# SMD_cree_driver_led-mosfet0024-GoldPhoen.net
KiCad netlist of a schematic drawn in EAGLE
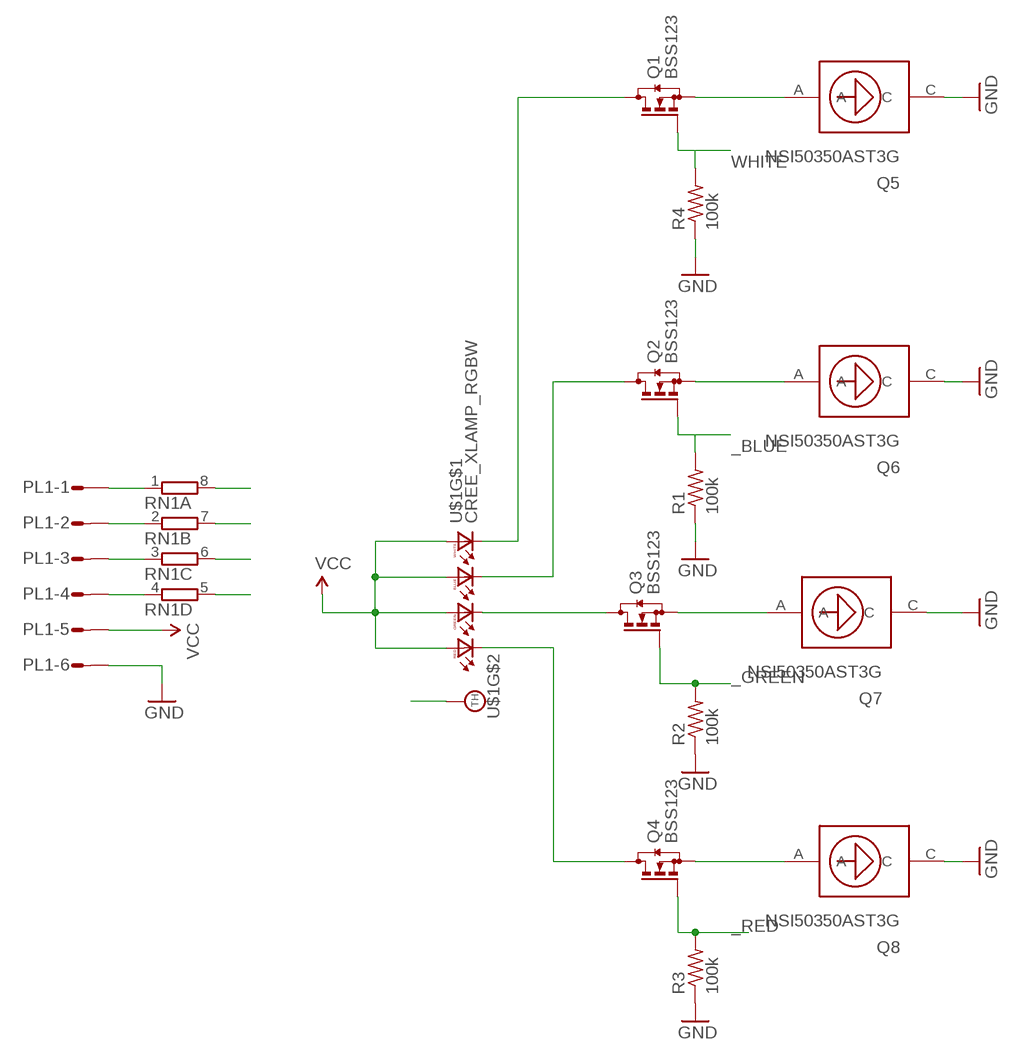
[diagram p0: schematic, sheet 1]

(export (version "E")
  (design (tool "Eeschema 10.0.6"))
  (components
    (comp (ref "PL1")
      (value "DF3-06R")
      (footprint "eagle-import:DF3R-06")
      (libsource (lib "eagle-import") (part "DF3-06R"))
    )
    (comp (ref "Q1")
      (value "BSS123")
      (footprint "eagle-import:SOT23")
      (libsource (lib "eagle-import") (part "BSS123"))
    )
    (comp (ref "Q2")
      (value "BSS123")
      (footprint "eagle-import:SOT23")
      (libsource (lib "eagle-import") (part "BSS123"))
    )
    (comp (ref "Q3")
      (value "BSS123")
      (footprint "eagle-import:SOT23")
      (libsource (lib "eagle-import") (part "BSS123"))
    )
    (comp (ref "Q4")
      (value "BSS123")
      (footprint "eagle-import:SOT23")
      (libsource (lib "eagle-import") (part "BSS123"))
    )
    (comp (ref "Q5")
      (value "NSI50350AST3G")
      (footprint "eagle-import:SMC-2")
      (libsource (lib "eagle-import") (part "NSI50350AST3G"))
    )
    (comp (ref "Q6")
      (value "NSI50350AST3G")
      (footprint "eagle-import:SMC-2")
      (libsource (lib "eagle-import") (part "NSI50350AST3G"))
    )
    (comp (ref "Q7")
      (value "NSI50350AST3G")
      (footprint "eagle-import:SMC-2")
      (libsource (lib "eagle-import") (part "NSI50350AST3G"))
    )
    (comp (ref "Q8")
      (value "NSI50350AST3G")
      (footprint "eagle-import:SMC-2")
      (libsource (lib "eagle-import") (part "NSI50350AST3G"))
    )
    (comp (ref "R1")
      (value "100k")
      (footprint "eagle-import:R0402")
      (libsource (lib "eagle-import") (part "R-US_R0402"))
    )
    (comp (ref "R2")
      (value "100k")
      (footprint "eagle-import:R0402")
      (libsource (lib "eagle-import") (part "R-US_R0402"))
    )
    (comp (ref "R3")
      (value "100k")
      (footprint "eagle-import:R0402")
      (libsource (lib "eagle-import") (part "R-US_R0402"))
    )
    (comp (ref "R4")
      (value "100k")
      (footprint "eagle-import:R0402")
      (libsource (lib "eagle-import") (part "R-US_R0402"))
    )
    (comp (ref "RN1")
      (value "4R-N0603-ARC")
      (footprint "eagle-import:0603-ARC")
      (libsource (lib "eagle-import") (part "4R-N0603-ARC"))
    )
    (comp (ref "U$1")
      (value "CREE_XLAMP_RGBW")
      (footprint "eagle-import:CREE_XLAMP_XML")
      (libsource (lib "eagle-import") (part "CREE_XLAMP_RGBW"))
    )
  )
  (nets
    (net (code "1") (name "/WHITE") (class "Default")
      (node (ref "Q1") (pin "1") (pinfunction "G_1") (pintype "passive"))
      (node (ref "R4") (pin "2") (pinfunction "2_2") (pintype "passive"))
      (node (ref "RN1") (pin "8") (pinfunction "2_8") (pintype "passive"))
    )
    (net (code "2") (name "/_BLUE") (class "Default")
      (node (ref "Q2") (pin "1") (pinfunction "G_1") (pintype "passive"))
      (node (ref "R1") (pin "2") (pinfunction "2_2") (pintype "passive"))
      (node (ref "RN1") (pin "6") (pinfunction "2_6") (pintype "passive"))
    )
    (net (code "3") (name "/_GREEN") (class "Default")
      (node (ref "Q3") (pin "1") (pinfunction "G_1") (pintype "passive"))
      (node (ref "R2") (pin "2") (pinfunction "2_2") (pintype "passive"))
      (node (ref "RN1") (pin "5") (pinfunction "2_5") (pintype "passive"))
    )
    (net (code "4") (name "/_RED") (class "Default")
      (node (ref "Q4") (pin "1") (pinfunction "G_1") (pintype "passive"))
      (node (ref "R3") (pin "2") (pinfunction "2_2") (pintype "passive"))
      (node (ref "RN1") (pin "7") (pinfunction "2_7") (pintype "passive"))
    )
    (net (code "5") (name "GND") (class "Default")
      (node (ref "PL1") (pin "6") (pinfunction "S_6") (pintype "passive"))
      (node (ref "Q5") (pin "C") (pinfunction "C_C") (pintype "bidirectional"))
      (node (ref "Q6") (pin "C") (pinfunction "C_C") (pintype "bidirectional"))
      (node (ref "Q7") (pin "C") (pinfunction "C_C") (pintype "bidirectional"))
      (node (ref "Q8") (pin "C") (pinfunction "C_C") (pintype "bidirectional"))
      (node (ref "R1") (pin "1") (pinfunction "1_1") (pintype "passive"))
      (node (ref "R2") (pin "1") (pinfunction "1_1") (pintype "passive"))
      (node (ref "R3") (pin "1") (pinfunction "1_1") (pintype "passive"))
      (node (ref "R4") (pin "1") (pinfunction "1_1") (pintype "passive"))
    )
    (net (code "6") (name "Net-(PL1A-S)") (class "Default")
      (node (ref "PL1") (pin "1") (pinfunction "S_1") (pintype "passive"))
      (node (ref "RN1") (pin "1") (pinfunction "1_1") (pintype "passive"))
    )
    (net (code "7") (name "Net-(PL1B-S)") (class "Default")
      (node (ref "PL1") (pin "2") (pinfunction "S_2") (pintype "passive"))
      (node (ref "RN1") (pin "2") (pinfunction "1_2") (pintype "passive"))
    )
    (net (code "8") (name "Net-(PL1C-S)") (class "Default")
      (node (ref "PL1") (pin "3") (pinfunction "S_3") (pintype "passive"))
      (node (ref "RN1") (pin "3") (pinfunction "1_3") (pintype "passive"))
    )
    (net (code "9") (name "Net-(PL1D-S)") (class "Default")
      (node (ref "PL1") (pin "4") (pinfunction "S_4") (pintype "passive"))
      (node (ref "RN1") (pin "4") (pinfunction "1_4") (pintype "passive"))
    )
    (net (code "10") (name "Net-(Q1-D)") (class "Default")
      (node (ref "Q1") (pin "3") (pinfunction "D_3") (pintype "passive"))
      (node (ref "U$1") (pin "5") (pinfunction "WC_5") (pintype "passive"))
    )
    (net (code "11") (name "Net-(Q1-S)") (class "Default")
      (node (ref "Q1") (pin "2") (pinfunction "S_2") (pintype "passive"))
      (node (ref "Q5") (pin "A") (pinfunction "A_A") (pintype "bidirectional"))
    )
    (net (code "12") (name "Net-(Q2-D)") (class "Default")
      (node (ref "Q2") (pin "3") (pinfunction "D_3") (pintype "passive"))
      (node (ref "U$1") (pin "6") (pinfunction "BC_6") (pintype "passive"))
    )
    (net (code "13") (name "Net-(Q2-S)") (class "Default")
      (node (ref "Q2") (pin "2") (pinfunction "S_2") (pintype "passive"))
      (node (ref "Q6") (pin "A") (pinfunction "A_A") (pintype "bidirectional"))
    )
    (net (code "14") (name "Net-(Q3-D)") (class "Default")
      (node (ref "Q3") (pin "3") (pinfunction "D_3") (pintype "passive"))
      (node (ref "U$1") (pin "7") (pinfunction "GC_7") (pintype "passive"))
    )
    (net (code "15") (name "Net-(Q3-S)") (class "Default")
      (node (ref "Q3") (pin "2") (pinfunction "S_2") (pintype "passive"))
      (node (ref "Q7") (pin "A") (pinfunction "A_A") (pintype "bidirectional"))
    )
    (net (code "16") (name "Net-(Q4-D)") (class "Default")
      (node (ref "Q4") (pin "3") (pinfunction "D_3") (pintype "passive"))
      (node (ref "U$1") (pin "8") (pinfunction "RC_8") (pintype "passive"))
    )
    (net (code "17") (name "Net-(Q4-S)") (class "Default")
      (node (ref "Q4") (pin "2") (pinfunction "S_2") (pintype "passive"))
      (node (ref "Q8") (pin "A") (pinfunction "A_A") (pintype "bidirectional"))
    )
    (net (code "18") (name "VCC") (class "Default")
      (node (ref "PL1") (pin "5") (pinfunction "S_5") (pintype "passive"))
      (node (ref "U$1") (pin "1") (pinfunction "RA_1") (pintype "passive"))
      (node (ref "U$1") (pin "2") (pinfunction "GA_2") (pintype "passive"))
      (node (ref "U$1") (pin "3") (pinfunction "BA_3") (pintype "passive"))
      (node (ref "U$1") (pin "4") (pinfunction "WA_4") (pintype "passive"))
    )
    (net (code "19") (name "unconnected-(U$1B-TH-PadP$1)") (class "Default")
      (node (ref "U$1") (pin "P$1") (pinfunction "TH_P$1") (pintype "passive"))
    )
  )
)
